# WiFi_Shield_Schematic.net
KiCad netlist of a schematic drawn in Altium Designer
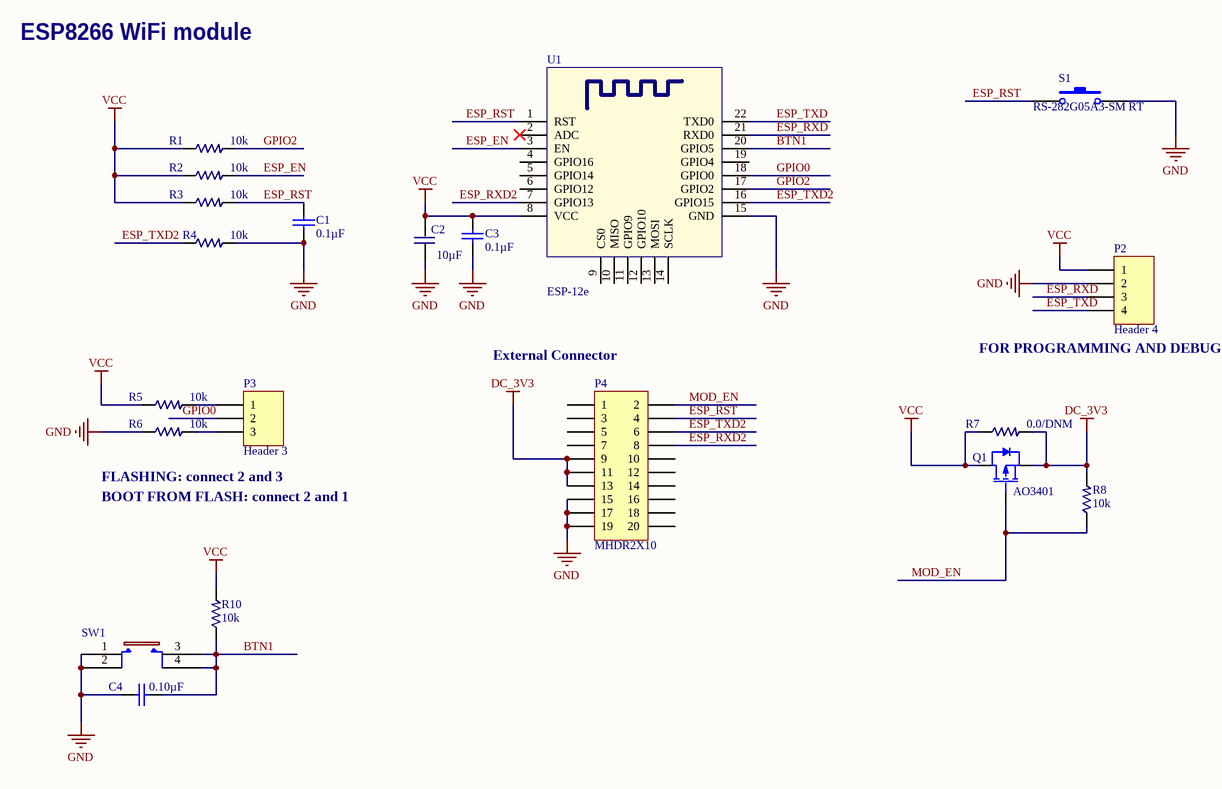
[diagram p0: WiFi Shield Schematic.SchDoc]

(export (version "E")
  (design (tool "Eeschema 10.0.6"))
  (components
    (comp (ref "C1")
      (value "0.1µF")
      (footprint "C0402M")
      (fields
        (field (name "MANUFACTURER") "Murata Electronics North America")
        (field (name "MANUFACTURER PART NUMBER") "GRM155R61C104KA88J")
        (field (name "TOLERANCE") "±10%")
      )
      (libsource (lib "blueThermoSchlib") (part "CAPN"))
    )
    (comp (ref "C2")
      (value "10µF")
      (footprint "C0603M")
      (description "CAP CER 10UF 10V X5R 0603")
      (fields
        (field (name "MANUFACTURER") "Taiyo Yuden")
        (field (name "MANUFACTURER PART NUMBER") "LMK107BBJ106MAHT")
      )
      (libsource (lib "BLE") (part "CAPSMD"))
    )
    (comp (ref "C3")
      (value "0.1µF")
      (footprint "C0402M")
      (fields
        (field (name "MANUFACTURER") "Murata Electronics North America")
        (field (name "MANUFACTURER PART NUMBER") "GRM155R61C104KA88J")
        (field (name "TOLERANCE") "±10%")
      )
      (libsource (lib "blueThermoSchlib") (part "CAPN"))
    )
    (comp (ref "C4")
      (value "0.10µF")
      (footprint "C0402M")
      (description "CAP CER 0.1UF 10V X5R 0402")
      (fields
        (field (name "MANUFACTURER") "Taiyo Yuden")
        (field (name "MANUFACTURER PART NUMBER") "LMK105BJ104KV-F")
      )
      (libsource (lib "blueThermoSchlib") (part "CAPN"))
    )
    (comp (ref "P2")
      (value "Header 4")
      (footprint "HDR1X4")
      (description "Header, 4-Pin")
      (fields (field (name "PUBLISHER") "Altium Limited"))
      (libsource (lib "Miscellaneous Connectors") (part "Header 4"))
    )
    (comp (ref "P3")
      (value "Header 3")
      (footprint "HDR1X3")
      (description "Header, 3-Pin")
      (fields (field (name "PUBLISHER") "Altium Limited"))
      (libsource (lib "Miscellaneous Connectors") (part "Header 3"))
    )
    (comp (ref "P4")
      (value "MHDR2X10")
      (footprint "MHDR2X10SMDM")
      (description "Header, 10-Pin, Dual row")
      (fields (field (name "PUBLISHER") "Altium Limited"))
      (libsource (lib "BinhLib") (part "MHDR2X10"))
    )
    (comp (ref "Q1")
      (value "AO3401")
      (footprint "SOT95P240X120-3N")
      (description "P-Channel MOSFET")
      (libsource (lib "BinhLib") (part "MOSFET-P1"))
    )
    (comp (ref "R1")
      (value "10k")
      (footprint "R0402M")
      (description "RES SMD 10K OHM 1% 1/16W 0402")
      (fields
        (field (name "MANUFACTURER") "Vishay Dale")
        (field (name "MANUFACTURER PART NUMBER") "CRCW040210K0FKEDC")
      )
      (libsource (lib "BLE") (part "RES_SMD"))
    )
    (comp (ref "R2")
      (value "10k")
      (footprint "R0402M")
      (description "RES SMD 10K OHM 1% 1/16W 0402")
      (fields
        (field (name "MANUFACTURER") "Vishay Dale")
        (field (name "MANUFACTURER PART NUMBER") "CRCW040210K0FKEDC")
      )
      (libsource (lib "BLE") (part "RES_SMD"))
    )
    (comp (ref "R3")
      (value "10k")
      (footprint "R0402M")
      (description "RES SMD 10K OHM 1% 1/16W 0402")
      (fields
        (field (name "MANUFACTURER") "Vishay Dale")
        (field (name "MANUFACTURER PART NUMBER") "CRCW040210K0FKEDC")
      )
      (libsource (lib "BLE") (part "RES_SMD"))
    )
    (comp (ref "R4")
      (value "10k")
      (footprint "R0402M")
      (description "RES SMD 10K OHM 1% 1/16W 0402")
      (fields
        (field (name "MANUFACTURER") "Vishay Dale")
        (field (name "MANUFACTURER PART NUMBER") "CRCW040210K0FKEDC")
      )
      (libsource (lib "BLE") (part "RES_SMD"))
    )
    (comp (ref "R5")
      (value "10k")
      (footprint "R0402M")
      (description "RES SMD 10K OHM 1% 1/16W 0402")
      (fields
        (field (name "MANUFACTURER") "Vishay Dale")
        (field (name "MANUFACTURER PART NUMBER") "CRCW040210K0FKEDC")
      )
      (libsource (lib "BLE") (part "RES_SMD"))
    )
    (comp (ref "R6")
      (value "10k")
      (footprint "R0402M")
      (description "RES SMD 10K OHM 1% 1/16W 0402")
      (fields
        (field (name "MANUFACTURER") "Vishay Dale")
        (field (name "MANUFACTURER PART NUMBER") "CRCW040210K0FKEDC")
      )
      (libsource (lib "BLE") (part "RES_SMD"))
    )
    (comp (ref "R7") (value "0.0/DNM") (footprint "R0805M") (libsource (lib "BLE") (part "RES_SMD")))
    (comp (ref "R8")
      (value "10k")
      (footprint "R0402M")
      (description "RES SMD 10K OHM 1% 1/16W 0402")
      (fields
        (field (name "MANUFACTURER") "Vishay Dale")
        (field (name "MANUFACTURER PART NUMBER") "CRCW040210K0FKEDC")
      )
      (libsource (lib "BLE") (part "RES_SMD"))
    )
    (comp (ref "R10")
      (value "10k")
      (footprint "R0402M")
      (description "RES SMD 10K OHM 1% 1/16W 0402")
      (fields (field (name "TOLERANCE") "±1%"))
      (libsource (lib "BLE") (part "RES_SMD"))
    )
    (comp (ref "S1")
      (value "RS-282G05A3-SM RT")
      (footprint "RS-282G05A3")
      (description "SWITCH TACTILE SPST-NO 0.05A 12V")
      (fields (field (name "MANUFACTURER") "C&K"))
      (libsource (lib "Miscellaneous Devices") (part "SW-PB"))
    )
    (comp (ref "SW1")
      (value "PTS645SL70SMTR92LFS")
      (footprint "PTS645SL70SMTR92LFS")
      (description "SWITCH TACTILE SPST-NO 0.05A 12V")
      (libsource (lib "AltiumDbLib") (part "PUSHBUTTON1"))
    )
    (comp (ref "U1")
      (value "ESP-12e")
      (footprint "ESP-12E")
      (description "ESP8266 SMT MODULE")
      (fields
        (field (name "MANUFACTURER") "Adafruit Industries LLC")
        (field (name "MANUFACTURER PART NUMBER") "2491")
      )
      (libsource (lib "BLE") (part "ESP-12e"))
    )
  )
  (nets
    (net (code "1") (name "/BTN1") (class "Default")
      (node (ref "C4") (pin "1") (pinfunction "1_1") (pintype "passive"))
      (node (ref "R10") (pin "2") (pinfunction "2_2") (pintype "passive"))
      (node (ref "SW1") (pin "3") (pinfunction "3_3") (pintype "passive"))
      (node (ref "SW1") (pin "4") (pinfunction "4_4") (pintype "passive"))
      (node (ref "U1") (pin "20") (pinfunction "GPIO5_20") (pintype "passive"))
    )
    (net (code "2") (name "/ESP_EN") (class "Default")
      (node (ref "R2") (pin "1") (pinfunction "1_1") (pintype "passive"))
      (node (ref "U1") (pin "3") (pinfunction "EN_3") (pintype "passive"))
    )
    (net (code "3") (name "/ESP_RST") (class "Default")
      (node (ref "C1") (pin "1") (pinfunction "1_1") (pintype "passive"))
      (node (ref "P4") (pin "4") (pinfunction "4_4") (pintype "passive"))
      (node (ref "R3") (pin "1") (pinfunction "1_1") (pintype "passive"))
      (node (ref "S1") (pin "1") (pinfunction "1_1") (pintype "passive"))
      (node (ref "U1") (pin "1") (pinfunction "RST_1") (pintype "passive"))
    )
    (net (code "4") (name "/ESP_RXD") (class "Default")
      (node (ref "P2") (pin "3") (pinfunction "3_3") (pintype "passive"))
      (node (ref "U1") (pin "21") (pinfunction "RXD0_21") (pintype "passive"))
    )
    (net (code "5") (name "/ESP_RXD2") (class "Default")
      (node (ref "P4") (pin "8") (pinfunction "8_8") (pintype "passive"))
      (node (ref "U1") (pin "7") (pinfunction "GPIO13_7") (pintype "passive"))
    )
    (net (code "6") (name "/ESP_TXD") (class "Default")
      (node (ref "P2") (pin "4") (pinfunction "4_4") (pintype "passive"))
      (node (ref "U1") (pin "22") (pinfunction "TXD0_22") (pintype "passive"))
    )
    (net (code "7") (name "/ESP_TXD2") (class "Default")
      (node (ref "P4") (pin "6") (pinfunction "6_6") (pintype "passive"))
      (node (ref "R4") (pin "2") (pinfunction "2_2") (pintype "passive"))
      (node (ref "U1") (pin "16") (pinfunction "GPIO15_16") (pintype "passive"))
    )
    (net (code "8") (name "/GPIO0") (class "Default")
      (node (ref "P3") (pin "2") (pinfunction "2_2") (pintype "passive"))
      (node (ref "U1") (pin "18") (pinfunction "GPIO0_18") (pintype "passive"))
    )
    (net (code "9") (name "/GPIO2") (class "Default")
      (node (ref "R1") (pin "1") (pinfunction "1_1") (pintype "passive"))
      (node (ref "U1") (pin "17") (pinfunction "GPIO2_17") (pintype "passive"))
    )
    (net (code "10") (name "/MOD_EN") (class "Default")
      (node (ref "P4") (pin "2") (pinfunction "2_2") (pintype "passive"))
      (node (ref "Q1") (pin "1") (pinfunction "G_1") (pintype "passive"))
      (node (ref "R8") (pin "2") (pinfunction "2_2") (pintype "passive"))
    )
    (net (code "11") (name "DC_3V3") (class "Default")
      (node (ref "P4") (pin "11") (pinfunction "11_11") (pintype "passive"))
      (node (ref "P4") (pin "13") (pinfunction "13_13") (pintype "passive"))
      (node (ref "P4") (pin "9") (pinfunction "9_9") (pintype "passive"))
      (node (ref "Q1") (pin "2") (pinfunction "S_2") (pintype "passive"))
      (node (ref "R7") (pin "1") (pinfunction "1_1") (pintype "passive"))
      (node (ref "R8") (pin "1") (pinfunction "1_1") (pintype "passive"))
    )
    (net (code "12") (name "GND") (class "Default")
      (node (ref "C1") (pin "2") (pinfunction "2_2") (pintype "passive"))
      (node (ref "C2") (pin "1") (pinfunction "1_1") (pintype "passive"))
      (node (ref "C3") (pin "2") (pinfunction "2_2") (pintype "passive"))
      (node (ref "C4") (pin "2") (pinfunction "2_2") (pintype "passive"))
      (node (ref "P2") (pin "2") (pinfunction "2_2") (pintype "passive"))
      (node (ref "P4") (pin "15") (pinfunction "15_15") (pintype "passive"))
      (node (ref "P4") (pin "17") (pinfunction "17_17") (pintype "passive"))
      (node (ref "P4") (pin "19") (pinfunction "19_19") (pintype "passive"))
      (node (ref "R4") (pin "1") (pinfunction "1_1") (pintype "passive"))
      (node (ref "R6") (pin "2") (pinfunction "2_2") (pintype "passive"))
      (node (ref "S1") (pin "2") (pinfunction "2_2") (pintype "passive"))
      (node (ref "SW1") (pin "1") (pinfunction "1_1") (pintype "passive"))
      (node (ref "SW1") (pin "2") (pinfunction "2_2") (pintype "passive"))
      (node (ref "U1") (pin "15") (pinfunction "GND_15") (pintype "passive"))
    )
    (net (code "13") (name "Net-(P3-Pad1)") (class "Default")
      (node (ref "P3") (pin "1") (pinfunction "1_1") (pintype "passive"))
      (node (ref "R5") (pin "1") (pinfunction "1_1") (pintype "passive"))
    )
    (net (code "14") (name "Net-(P3-Pad3)") (class "Default")
      (node (ref "P3") (pin "3") (pinfunction "3_3") (pintype "passive"))
      (node (ref "R6") (pin "1") (pinfunction "1_1") (pintype "passive"))
    )
    (net (code "15") (name "VCC") (class "Default")
      (node (ref "C2") (pin "2") (pinfunction "2_2") (pintype "passive"))
      (node (ref "C3") (pin "1") (pinfunction "1_1") (pintype "passive"))
      (node (ref "P2") (pin "1") (pinfunction "1_1") (pintype "passive"))
      (node (ref "Q1") (pin "3") (pinfunction "D_3") (pintype "passive"))
      (node (ref "R1") (pin "2") (pinfunction "2_2") (pintype "passive"))
      (node (ref "R10") (pin "1") (pinfunction "1_1") (pintype "passive"))
      (node (ref "R2") (pin "2") (pinfunction "2_2") (pintype "passive"))
      (node (ref "R3") (pin "2") (pinfunction "2_2") (pintype "passive"))
      (node (ref "R5") (pin "2") (pinfunction "2_2") (pintype "passive"))
      (node (ref "R7") (pin "2") (pinfunction "2_2") (pintype "passive"))
      (node (ref "U1") (pin "8") (pinfunction "VCC_8") (pintype "passive"))
    )
    (net (code "16") (name "unconnected-(P4-Pad1)") (class "Default")
      (node (ref "P4") (pin "1") (pinfunction "1_1") (pintype "passive"))
    )
    (net (code "17") (name "unconnected-(P4-Pad3)") (class "Default")
      (node (ref "P4") (pin "3") (pinfunction "3_3") (pintype "passive"))
    )
    (net (code "18") (name "unconnected-(P4-Pad5)") (class "Default")
      (node (ref "P4") (pin "5") (pinfunction "5_5") (pintype "passive"))
    )
    (net (code "19") (name "unconnected-(P4-Pad7)") (class "Default")
      (node (ref "P4") (pin "7") (pinfunction "7_7") (pintype "passive"))
    )
    (net (code "20") (name "unconnected-(P4-Pad10)") (class "Default")
      (node (ref "P4") (pin "10") (pinfunction "10_10") (pintype "passive"))
    )
    (net (code "21") (name "unconnected-(P4-Pad12)") (class "Default")
      (node (ref "P4") (pin "12") (pinfunction "12_12") (pintype "passive"))
    )
    (net (code "22") (name "unconnected-(P4-Pad14)") (class "Default")
      (node (ref "P4") (pin "14") (pinfunction "14_14") (pintype "passive"))
    )
    (net (code "23") (name "unconnected-(P4-Pad16)") (class "Default")
      (node (ref "P4") (pin "16") (pinfunction "16_16") (pintype "passive"))
    )
    (net (code "24") (name "unconnected-(P4-Pad18)") (class "Default")
      (node (ref "P4") (pin "18") (pinfunction "18_18") (pintype "passive"))
    )
    (net (code "25") (name "unconnected-(P4-Pad20)") (class "Default")
      (node (ref "P4") (pin "20") (pinfunction "20_20") (pintype "passive"))
    )
    (net (code "26") (name "unconnected-(U1-ADC-Pad2)") (class "Default")
      (node (ref "U1") (pin "2") (pinfunction "ADC_2") (pintype "passive+no_connect"))
    )
    (net (code "27") (name "unconnected-(U1-CS0-Pad9)") (class "Default")
      (node (ref "U1") (pin "9") (pinfunction "CS0_9") (pintype "passive"))
    )
    (net (code "28") (name "unconnected-(U1-GPIO4-Pad19)") (class "Default")
      (node (ref "U1") (pin "19") (pinfunction "GPIO4_19") (pintype "passive"))
    )
    (net (code "29") (name "unconnected-(U1-GPIO9-Pad11)") (class "Default")
      (node (ref "U1") (pin "11") (pinfunction "GPIO9_11") (pintype "passive"))
    )
    (net (code "30") (name "unconnected-(U1-GPIO10-Pad12)") (class "Default")
      (node (ref "U1") (pin "12") (pinfunction "GPIO10_12") (pintype "passive"))
    )
    (net (code "31") (name "unconnected-(U1-GPIO12-Pad6)") (class "Default")
      (node (ref "U1") (pin "6") (pinfunction "GPIO12_6") (pintype "passive"))
    )
    (net (code "32") (name "unconnected-(U1-GPIO14-Pad5)") (class "Default")
      (node (ref "U1") (pin "5") (pinfunction "GPIO14_5") (pintype "passive"))
    )
    (net (code "33") (name "unconnected-(U1-GPIO16-Pad4)") (class "Default")
      (node (ref "U1") (pin "4") (pinfunction "GPIO16_4") (pintype "passive"))
    )
    (net (code "34") (name "unconnected-(U1-MISO-Pad10)") (class "Default")
      (node (ref "U1") (pin "10") (pinfunction "MISO_10") (pintype "passive"))
    )
    (net (code "35") (name "unconnected-(U1-MOSI-Pad13)") (class "Default")
      (node (ref "U1") (pin "13") (pinfunction "MOSI_13") (pintype "passive"))
    )
    (net (code "36") (name "unconnected-(U1-SCLK-Pad14)") (class "Default")
      (node (ref "U1") (pin "14") (pinfunction "SCLK_14") (pintype "passive"))
    )
  )
)
